# Pro_Trinket_Keyboard_V3_4_a.net
KiCad netlist of a schematic drawn in EAGLE
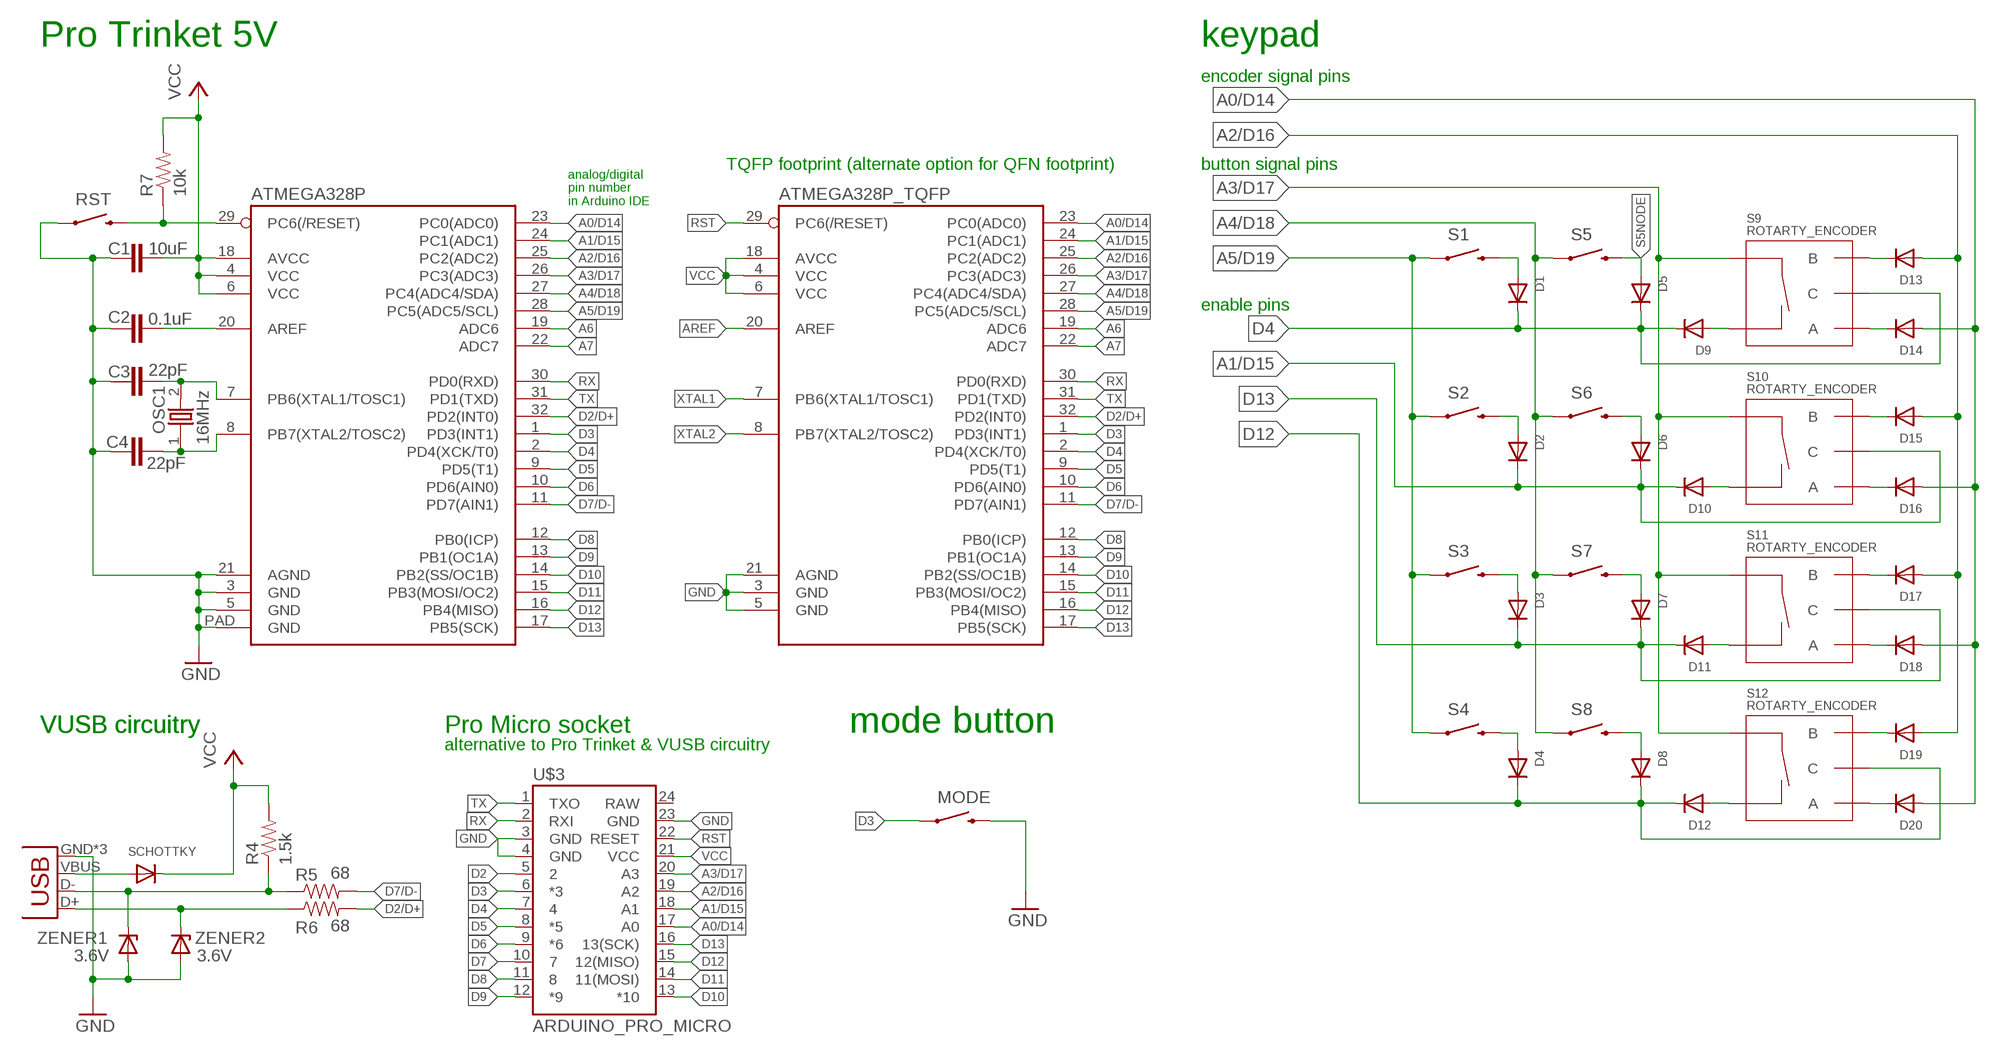
[diagram p0: schematic, sheet 1, part 1 of 2]
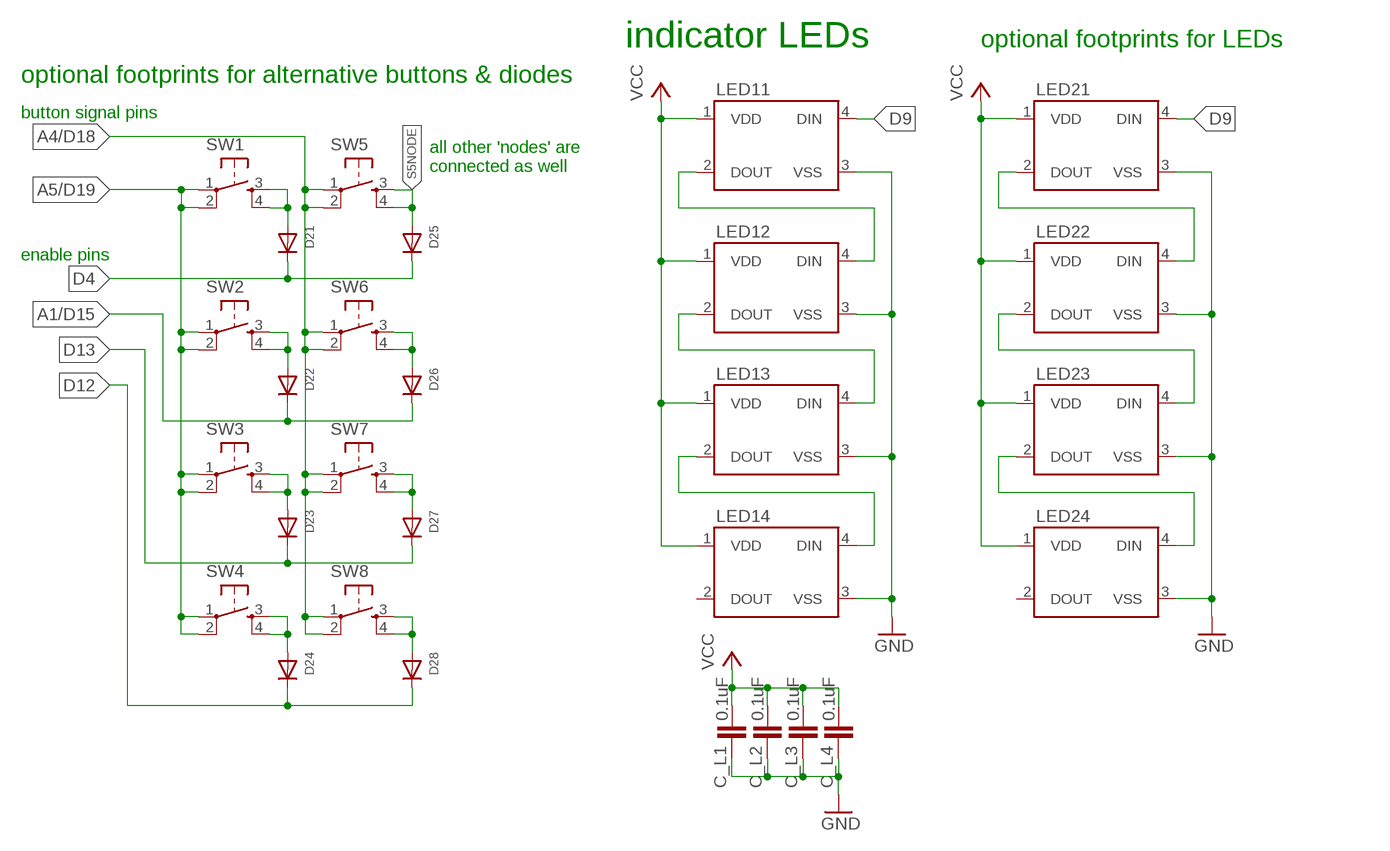
[diagram p1: schematic, sheet 1, part 2 of 2]

(export (version "E")
  (design (tool "Eeschema 10.0.6"))
  (components
    (comp (ref "ATMEGA328P")
      (value "ATMEGA328P_MLFMLF32")
      (footprint "eagle-import:MLF32-PAD")
      (libsource (lib "eagle-import") (part "ATMEGA328P_MLFMLF32"))
    )
    (comp (ref "ATMEGA328P_TQFP")
      (value "ATMEGA328P_TQFP")
      (footprint "eagle-import:TQFP32-08")
      (libsource (lib "eagle-import") (part "ATMEGA328P_TQFP"))
    )
    (comp (ref "C1")
      (value "10uF")
      (footprint "eagle-import:0603-CAP")
      (libsource (lib "eagle-import") (part "10UF-6.3V-20%(0603)"))
    )
    (comp (ref "C2")
      (value "0.1uF")
      (footprint "eagle-import:0603-CAP")
      (libsource (lib "eagle-import") (part "22PF-50V-5%(0603)"))
    )
    (comp (ref "C3")
      (value "22pF")
      (footprint "eagle-import:0603-CAP")
      (libsource (lib "eagle-import") (part "22PF-50V-5%(0603)"))
    )
    (comp (ref "C4")
      (value "22pF")
      (footprint "eagle-import:0603-CAP")
      (libsource (lib "eagle-import") (part "22PF-50V-5%(0603)"))
    )
    (comp (ref "C_L1")
      (value "0.1uF")
      (footprint "eagle-import:0603-CAP")
      (libsource (lib "eagle-import") (part "22PF-50V-5%(0603)"))
    )
    (comp (ref "C_L2")
      (value "0.1uF")
      (footprint "eagle-import:0603-CAP")
      (libsource (lib "eagle-import") (part "22PF-50V-5%(0603)"))
    )
    (comp (ref "C_L3")
      (value "0.1uF")
      (footprint "eagle-import:0603-CAP")
      (libsource (lib "eagle-import") (part "22PF-50V-5%(0603)"))
    )
    (comp (ref "C_L4")
      (value "0.1uF")
      (footprint "eagle-import:0603-CAP")
      (libsource (lib "eagle-import") (part "22PF-50V-5%(0603)"))
    )
    (comp (ref "D1")
      (value "DIODESOD-123")
      (footprint "eagle-import:SOD-123")
      (libsource (lib "eagle-import") (part "DIODESOD-123"))
    )
    (comp (ref "D2")
      (value "DIODESOD-123")
      (footprint "eagle-import:SOD-123")
      (libsource (lib "eagle-import") (part "DIODESOD-123"))
    )
    (comp (ref "D3")
      (value "DIODESOD-123")
      (footprint "eagle-import:SOD-123")
      (libsource (lib "eagle-import") (part "DIODESOD-123"))
    )
    (comp (ref "D4")
      (value "DIODESOD-123")
      (footprint "eagle-import:SOD-123")
      (libsource (lib "eagle-import") (part "DIODESOD-123"))
    )
    (comp (ref "D5")
      (value "DIODESOD-123")
      (footprint "eagle-import:SOD-123")
      (libsource (lib "eagle-import") (part "DIODESOD-123"))
    )
    (comp (ref "D6")
      (value "DIODESOD-123")
      (footprint "eagle-import:SOD-123")
      (libsource (lib "eagle-import") (part "DIODESOD-123"))
    )
    (comp (ref "D7")
      (value "DIODESOD-123")
      (footprint "eagle-import:SOD-123")
      (libsource (lib "eagle-import") (part "DIODESOD-123"))
    )
    (comp (ref "D8")
      (value "DIODESOD-123")
      (footprint "eagle-import:SOD-123")
      (libsource (lib "eagle-import") (part "DIODESOD-123"))
    )
    (comp (ref "D9")
      (value "DIODESOD-123")
      (footprint "eagle-import:SOD-123")
      (libsource (lib "eagle-import") (part "DIODESOD-123"))
    )
    (comp (ref "D10")
      (value "DIODESOD-123")
      (footprint "eagle-import:SOD-123")
      (libsource (lib "eagle-import") (part "DIODESOD-123"))
    )
    (comp (ref "D11")
      (value "DIODESOD-123")
      (footprint "eagle-import:SOD-123")
      (libsource (lib "eagle-import") (part "DIODESOD-123"))
    )
    (comp (ref "D12")
      (value "DIODESOD-123")
      (footprint "eagle-import:SOD-123")
      (libsource (lib "eagle-import") (part "DIODESOD-123"))
    )
    (comp (ref "D13")
      (value "DIODESOD-123")
      (footprint "eagle-import:SOD-123")
      (libsource (lib "eagle-import") (part "DIODESOD-123"))
    )
    (comp (ref "D14")
      (value "DIODESOD-123")
      (footprint "eagle-import:SOD-123")
      (libsource (lib "eagle-import") (part "DIODESOD-123"))
    )
    (comp (ref "D15")
      (value "DIODESOD-123")
      (footprint "eagle-import:SOD-123")
      (libsource (lib "eagle-import") (part "DIODESOD-123"))
    )
    (comp (ref "D16")
      (value "DIODESOD-123")
      (footprint "eagle-import:SOD-123")
      (libsource (lib "eagle-import") (part "DIODESOD-123"))
    )
    (comp (ref "D17")
      (value "DIODESOD-123")
      (footprint "eagle-import:SOD-123")
      (libsource (lib "eagle-import") (part "DIODESOD-123"))
    )
    (comp (ref "D18")
      (value "DIODESOD-123")
      (footprint "eagle-import:SOD-123")
      (libsource (lib "eagle-import") (part "DIODESOD-123"))
    )
    (comp (ref "D19")
      (value "DIODESOD-123")
      (footprint "eagle-import:SOD-123")
      (libsource (lib "eagle-import") (part "DIODESOD-123"))
    )
    (comp (ref "D20")
      (value "DIODESOD-123")
      (footprint "eagle-import:SOD-123")
      (libsource (lib "eagle-import") (part "DIODESOD-123"))
    )
    (comp (ref "D21")
      (value "DIODESOD-123")
      (footprint "eagle-import:SOD-123")
      (libsource (lib "eagle-import") (part "DIODESOD-123"))
    )
    (comp (ref "D22")
      (value "DIODESOD-123")
      (footprint "eagle-import:SOD-123")
      (libsource (lib "eagle-import") (part "DIODESOD-123"))
    )
    (comp (ref "D23")
      (value "DIODESOD-123")
      (footprint "eagle-import:SOD-123")
      (libsource (lib "eagle-import") (part "DIODESOD-123"))
    )
    (comp (ref "D24")
      (value "DIODESOD-123")
      (footprint "eagle-import:SOD-123")
      (libsource (lib "eagle-import") (part "DIODESOD-123"))
    )
    (comp (ref "D25")
      (value "DIODESOD-123")
      (footprint "eagle-import:SOD-123")
      (libsource (lib "eagle-import") (part "DIODESOD-123"))
    )
    (comp (ref "D26")
      (value "DIODESOD-123")
      (footprint "eagle-import:SOD-123")
      (libsource (lib "eagle-import") (part "DIODESOD-123"))
    )
    (comp (ref "D27")
      (value "DIODESOD-123")
      (footprint "eagle-import:SOD-123")
      (libsource (lib "eagle-import") (part "DIODESOD-123"))
    )
    (comp (ref "D28")
      (value "DIODESOD-123")
      (footprint "eagle-import:SOD-123")
      (libsource (lib "eagle-import") (part "DIODESOD-123"))
    )
    (comp (ref "LED11")
      (value "WS2812B")
      (footprint "eagle-import:WS2812B")
      (libsource (lib "eagle-import") (part "WS2812B"))
    )
    (comp (ref "LED12")
      (value "WS2812B")
      (footprint "eagle-import:WS2812B")
      (libsource (lib "eagle-import") (part "WS2812B"))
    )
    (comp (ref "LED13")
      (value "WS2812B")
      (footprint "eagle-import:WS2812B")
      (libsource (lib "eagle-import") (part "WS2812B"))
    )
    (comp (ref "LED14")
      (value "WS2812B")
      (footprint "eagle-import:WS2812B")
      (libsource (lib "eagle-import") (part "WS2812B"))
    )
    (comp (ref "LED21")
      (value "WS2812B")
      (footprint "eagle-import:WS2812B")
      (libsource (lib "eagle-import") (part "WS2812B"))
    )
    (comp (ref "LED22")
      (value "WS2812B")
      (footprint "eagle-import:WS2812B")
      (libsource (lib "eagle-import") (part "WS2812B"))
    )
    (comp (ref "LED23")
      (value "WS2812B")
      (footprint "eagle-import:WS2812B")
      (libsource (lib "eagle-import") (part "WS2812B"))
    )
    (comp (ref "LED24")
      (value "WS2812B")
      (footprint "eagle-import:WS2812B")
      (libsource (lib "eagle-import") (part "WS2812B"))
    )
    (comp (ref "MODE")
      (value "SWITCH-MOMENTARY-2SIDE_EZ")
      (footprint "eagle-import:TACTILE-PTH-SIDEEZ")
      (libsource (lib "eagle-import") (part "SWITCH-MOMENTARY-2SIDE_EZ"))
    )
    (comp (ref "OSC1")
      (value "16MHz")
      (footprint "eagle-import:HC-49U")
      (libsource (lib "eagle-import") (part "OSC-XTAL-HC-49U-SMD"))
    )
    (comp (ref "R4")
      (value "1.5k")
      (footprint "eagle-import:0805")
      (libsource (lib "eagle-import") (part "RESISTOR0805-RES"))
    )
    (comp (ref "R5")
      (value "68")
      (footprint "eagle-import:0805")
      (libsource (lib "eagle-import") (part "RESISTOR0805-RES"))
    )
    (comp (ref "R6")
      (value "68")
      (footprint "eagle-import:0805")
      (libsource (lib "eagle-import") (part "RESISTOR0805-RES"))
    )
    (comp (ref "R7")
      (value "10k")
      (footprint "eagle-import:0805")
      (libsource (lib "eagle-import") (part "RESISTOR0805-RES"))
    )
    (comp (ref "RST")
      (value "SWITCH-MOMENTARY-2SIDE_EZ")
      (footprint "eagle-import:TACTILE-PTH-SIDEEZ")
      (libsource (lib "eagle-import") (part "SWITCH-MOMENTARY-2SIDE_EZ"))
    )
    (comp (ref "S1")
      (value "SWITCH-MOMENTARY-212MM")
      (footprint "eagle-import:TACTILE-PTH-12MM")
      (libsource (lib "eagle-import") (part "SWITCH-MOMENTARY-212MM"))
    )
    (comp (ref "S2")
      (value "SWITCH-MOMENTARY-212MM")
      (footprint "eagle-import:TACTILE-PTH-12MM")
      (libsource (lib "eagle-import") (part "SWITCH-MOMENTARY-212MM"))
    )
    (comp (ref "S3")
      (value "SWITCH-MOMENTARY-212MM")
      (footprint "eagle-import:TACTILE-PTH-12MM")
      (libsource (lib "eagle-import") (part "SWITCH-MOMENTARY-212MM"))
    )
    (comp (ref "S4")
      (value "SWITCH-MOMENTARY-212MM")
      (footprint "eagle-import:TACTILE-PTH-12MM")
      (libsource (lib "eagle-import") (part "SWITCH-MOMENTARY-212MM"))
    )
    (comp (ref "S5")
      (value "SWITCH-MOMENTARY-212MM")
      (footprint "eagle-import:TACTILE-PTH-12MM")
      (libsource (lib "eagle-import") (part "SWITCH-MOMENTARY-212MM"))
    )
    (comp (ref "S6")
      (value "SWITCH-MOMENTARY-212MM")
      (footprint "eagle-import:TACTILE-PTH-12MM")
      (libsource (lib "eagle-import") (part "SWITCH-MOMENTARY-212MM"))
    )
    (comp (ref "S7")
      (value "SWITCH-MOMENTARY-212MM")
      (footprint "eagle-import:TACTILE-PTH-12MM")
      (libsource (lib "eagle-import") (part "SWITCH-MOMENTARY-212MM"))
    )
    (comp (ref "S8")
      (value "SWITCH-MOMENTARY-212MM")
      (footprint "eagle-import:TACTILE-PTH-12MM")
      (libsource (lib "eagle-import") (part "SWITCH-MOMENTARY-212MM"))
    )
    (comp (ref "S9")
      (value "ROTARTY_ENCODER")
      (footprint "eagle-import:ROTARY_ENC_PLAIN")
      (libsource (lib "eagle-import") (part "ROTARTY_ENCODER"))
    )
    (comp (ref "S10")
      (value "ROTARTY_ENCODER")
      (footprint "eagle-import:ROTARY_ENC_PLAIN")
      (libsource (lib "eagle-import") (part "ROTARTY_ENCODER"))
    )
    (comp (ref "S11")
      (value "ROTARTY_ENCODER")
      (footprint "eagle-import:ROTARY_ENC_PLAIN")
      (libsource (lib "eagle-import") (part "ROTARTY_ENCODER"))
    )
    (comp (ref "S12")
      (value "ROTARTY_ENCODER")
      (footprint "eagle-import:ROTARY_ENC_PLAIN")
      (libsource (lib "eagle-import") (part "ROTARTY_ENCODER"))
    )
    (comp (ref "SCHOTTKY")
      (value "DIODESMA")
      (footprint "eagle-import:SMADIODE")
      (libsource (lib "eagle-import") (part "DIODESMA"))
    )
    (comp (ref "SW1")
      (value "TACTILE-SWITCH-PTH")
      (footprint "eagle-import:TAC-SWITCH-PTH")
      (libsource (lib "eagle-import") (part "TACTILE-SWITCH-PTH"))
    )
    (comp (ref "SW2")
      (value "TACTILE-SWITCH-PTH")
      (footprint "eagle-import:TAC-SWITCH-PTH")
      (libsource (lib "eagle-import") (part "TACTILE-SWITCH-PTH"))
    )
    (comp (ref "SW3")
      (value "TACTILE-SWITCH-PTH")
      (footprint "eagle-import:TAC-SWITCH-PTH")
      (libsource (lib "eagle-import") (part "TACTILE-SWITCH-PTH"))
    )
    (comp (ref "SW4")
      (value "TACTILE-SWITCH-PTH")
      (footprint "eagle-import:TAC-SWITCH-PTH")
      (libsource (lib "eagle-import") (part "TACTILE-SWITCH-PTH"))
    )
    (comp (ref "SW5")
      (value "TACTILE-SWITCH-PTH")
      (footprint "eagle-import:TAC-SWITCH-PTH")
      (libsource (lib "eagle-import") (part "TACTILE-SWITCH-PTH"))
    )
    (comp (ref "SW6")
      (value "TACTILE-SWITCH-PTH")
      (footprint "eagle-import:TAC-SWITCH-PTH")
      (libsource (lib "eagle-import") (part "TACTILE-SWITCH-PTH"))
    )
    (comp (ref "SW7")
      (value "TACTILE-SWITCH-PTH")
      (footprint "eagle-import:TAC-SWITCH-PTH")
      (libsource (lib "eagle-import") (part "TACTILE-SWITCH-PTH"))
    )
    (comp (ref "SW8")
      (value "TACTILE-SWITCH-PTH")
      (footprint "eagle-import:TAC-SWITCH-PTH")
      (libsource (lib "eagle-import") (part "TACTILE-SWITCH-PTH"))
    )
    (comp (ref "U$3")
      (value "ARDUINO_PRO_MICRO")
      (footprint "eagle-import:ARDUINO_PRO_MICRO")
      (libsource (lib "eagle-import") (part "ARDUINO_PRO_MICRO"))
    )
    (comp (ref "UUSB")
      (value "USB-MICROB")
      (footprint "eagle-import:USB-MICROB")
      (libsource (lib "eagle-import") (part "USB-MICROB"))
    )
    (comp (ref "ZENER1")
      (value "3.6V")
      (footprint "eagle-import:SOD80C")
      (libsource (lib "eagle-import") (part "ZENER-DIODESOD80C"))
    )
    (comp (ref "ZENER2")
      (value "3.6V")
      (footprint "eagle-import:SOD80C")
      (libsource (lib "eagle-import") (part "ZENER-DIODESOD80C"))
    )
  )
  (nets
    (net (code "1") (name "/L1NODE") (class "Default")
      (node (ref "LED11") (pin "2") (pinfunction "DOUT_2") (pintype "output"))
      (node (ref "LED12") (pin "4") (pinfunction "DIN_4") (pintype "input"))
      (node (ref "LED21") (pin "2") (pinfunction "DOUT_2") (pintype "output"))
      (node (ref "LED22") (pin "4") (pinfunction "DIN_4") (pintype "input"))
    )
    (net (code "2") (name "/L2NODE") (class "Default")
      (node (ref "LED12") (pin "2") (pinfunction "DOUT_2") (pintype "output"))
      (node (ref "LED13") (pin "4") (pinfunction "DIN_4") (pintype "input"))
      (node (ref "LED22") (pin "2") (pinfunction "DOUT_2") (pintype "output"))
      (node (ref "LED23") (pin "4") (pinfunction "DIN_4") (pintype "input"))
    )
    (net (code "3") (name "/L3NODE") (class "Default")
      (node (ref "LED13") (pin "2") (pinfunction "DOUT_2") (pintype "output"))
      (node (ref "LED14") (pin "4") (pinfunction "DIN_4") (pintype "input"))
      (node (ref "LED23") (pin "2") (pinfunction "DOUT_2") (pintype "output"))
      (node (ref "LED24") (pin "4") (pinfunction "DIN_4") (pintype "input"))
    )
    (net (code "4") (name "/S1NODE") (class "Default")
      (node (ref "D1") (pin "A") (pinfunction "A_A") (pintype "passive"))
      (node (ref "D21") (pin "A") (pinfunction "A_A") (pintype "passive"))
      (node (ref "S1") (pin "3") (pinfunction "2_3") (pintype "passive"))
      (node (ref "S1") (pin "4") (pinfunction "2_4") (pintype "passive"))
      (node (ref "SW1") (pin "3") (pinfunction "3_3") (pintype "passive"))
      (node (ref "SW1") (pin "4") (pinfunction "4_4") (pintype "passive"))
    )
    (net (code "5") (name "/S2NODE") (class "Default")
      (node (ref "D2") (pin "A") (pinfunction "A_A") (pintype "passive"))
      (node (ref "D22") (pin "A") (pinfunction "A_A") (pintype "passive"))
      (node (ref "S2") (pin "3") (pinfunction "2_3") (pintype "passive"))
      (node (ref "S2") (pin "4") (pinfunction "2_4") (pintype "passive"))
      (node (ref "SW2") (pin "3") (pinfunction "3_3") (pintype "passive"))
      (node (ref "SW2") (pin "4") (pinfunction "4_4") (pintype "passive"))
    )
    (net (code "6") (name "/S3NODE") (class "Default")
      (node (ref "D23") (pin "A") (pinfunction "A_A") (pintype "passive"))
      (node (ref "D3") (pin "A") (pinfunction "A_A") (pintype "passive"))
      (node (ref "S3") (pin "3") (pinfunction "2_3") (pintype "passive"))
      (node (ref "S3") (pin "4") (pinfunction "2_4") (pintype "passive"))
      (node (ref "SW3") (pin "3") (pinfunction "3_3") (pintype "passive"))
      (node (ref "SW3") (pin "4") (pinfunction "4_4") (pintype "passive"))
    )
    (net (code "7") (name "/S4NODE") (class "Default")
      (node (ref "D24") (pin "A") (pinfunction "A_A") (pintype "passive"))
      (node (ref "D4") (pin "A") (pinfunction "A_A") (pintype "passive"))
      (node (ref "S4") (pin "3") (pinfunction "2_3") (pintype "passive"))
      (node (ref "S4") (pin "4") (pinfunction "2_4") (pintype "passive"))
      (node (ref "SW4") (pin "3") (pinfunction "3_3") (pintype "passive"))
      (node (ref "SW4") (pin "4") (pinfunction "4_4") (pintype "passive"))
    )
    (net (code "8") (name "/S6NODE") (class "Default")
      (node (ref "D26") (pin "A") (pinfunction "A_A") (pintype "passive"))
      (node (ref "D6") (pin "A") (pinfunction "A_A") (pintype "passive"))
      (node (ref "S6") (pin "3") (pinfunction "2_3") (pintype "passive"))
      (node (ref "S6") (pin "4") (pinfunction "2_4") (pintype "passive"))
      (node (ref "SW6") (pin "3") (pinfunction "3_3") (pintype "passive"))
      (node (ref "SW6") (pin "4") (pinfunction "4_4") (pintype "passive"))
    )
    (net (code "9") (name "/S7NODE") (class "Default")
      (node (ref "D27") (pin "A") (pinfunction "A_A") (pintype "passive"))
      (node (ref "D7") (pin "A") (pinfunction "A_A") (pintype "passive"))
      (node (ref "S7") (pin "3") (pinfunction "2_3") (pintype "passive"))
      (node (ref "S7") (pin "4") (pinfunction "2_4") (pintype "passive"))
      (node (ref "SW7") (pin "3") (pinfunction "3_3") (pintype "passive"))
      (node (ref "SW7") (pin "4") (pinfunction "4_4") (pintype "passive"))
    )
    (net (code "10") (name "/S8NODE") (class "Default")
      (node (ref "D28") (pin "A") (pinfunction "A_A") (pintype "passive"))
      (node (ref "D8") (pin "A") (pinfunction "A_A") (pintype "passive"))
      (node (ref "S8") (pin "3") (pinfunction "2_3") (pintype "passive"))
      (node (ref "S8") (pin "4") (pinfunction "2_4") (pintype "passive"))
      (node (ref "SW8") (pin "3") (pinfunction "3_3") (pintype "passive"))
      (node (ref "SW8") (pin "4") (pinfunction "4_4") (pintype "passive"))
    )
    (net (code "11") (name "A0{slash}D14") (class "Default")
      (node (ref "ATMEGA328P") (pin "23") (pinfunction "PC0(ADC0)_23") (pintype "bidirectional"))
      (node (ref "ATMEGA328P_TQFP") (pin "23") (pinfunction "PC0(ADC0)_23") (pintype "bidirectional"))
      (node (ref "D14") (pin "A") (pinfunction "A_A") (pintype "passive"))
      (node (ref "D16") (pin "A") (pinfunction "A_A") (pintype "passive"))
      (node (ref "D18") (pin "A") (pinfunction "A_A") (pintype "passive"))
      (node (ref "D20") (pin "A") (pinfunction "A_A") (pintype "passive"))
      (node (ref "U$3") (pin "17") (pinfunction "A0_17") (pintype "bidirectional"))
    )
    (net (code "12") (name "A1{slash}D15") (class "Default")
      (node (ref "ATMEGA328P") (pin "24") (pinfunction "PC1(ADC1)_24") (pintype "bidirectional"))
      (node (ref "ATMEGA328P_TQFP") (pin "24") (pinfunction "PC1(ADC1)_24") (pintype "bidirectional"))
      (node (ref "D10") (pin "C") (pinfunction "C_C") (pintype "passive"))
      (node (ref "D2") (pin "C") (pinfunction "C_C") (pintype "passive"))
      (node (ref "D22") (pin "C") (pinfunction "C_C") (pintype "passive"))
      (node (ref "D26") (pin "C") (pinfunction "C_C") (pintype "passive"))
      (node (ref "D6") (pin "C") (pinfunction "C_C") (pintype "passive"))
      (node (ref "S10") (pin "C") (pinfunction "C_C") (pintype "bidirectional"))
      (node (ref "U$3") (pin "18") (pinfunction "A1_18") (pintype "bidirectional"))
    )
    (net (code "13") (name "A2{slash}D16") (class "Default")
      (node (ref "ATMEGA328P") (pin "25") (pinfunction "PC2(ADC2)_25") (pintype "bidirectional"))
      (node (ref "ATMEGA328P_TQFP") (pin "25") (pinfunction "PC2(ADC2)_25") (pintype "bidirectional"))
      (node (ref "D13") (pin "A") (pinfunction "A_A") (pintype "passive"))
      (node (ref "D15") (pin "A") (pinfunction "A_A") (pintype "passive"))
      (node (ref "D17") (pin "A") (pinfunction "A_A") (pintype "passive"))
      (node (ref "D19") (pin "A") (pinfunction "A_A") (pintype "passive"))
      (node (ref "U$3") (pin "19") (pinfunction "A2_19") (pintype "bidirectional"))
    )
    (net (code "14") (name "A3{slash}D17") (class "Default")
      (node (ref "ATMEGA328P") (pin "26") (pinfunction "PC3(ADC3)_26") (pintype "bidirectional"))
      (node (ref "ATMEGA328P_TQFP") (pin "26") (pinfunction "PC3(ADC3)_26") (pintype "bidirectional"))
      (node (ref "S10") (pin "SW+") (pinfunction "SW+_SW+") (pintype "bidirectional"))
      (node (ref "S11") (pin "SW+") (pinfunction "SW+_SW+") (pintype "bidirectional"))
      (node (ref "S12") (pin "SW+") (pinfunction "SW+_SW+") (pintype "bidirectional"))
      (node (ref "S9") (pin "SW+") (pinfunction "SW+_SW+") (pintype "bidirectional"))
      (node (ref "U$3") (pin "20") (pinfunction "A3_20") (pintype "bidirectional"))
    )
    (net (code "15") (name "A4{slash}D18") (class "Default")
      (node (ref "ATMEGA328P") (pin "27") (pinfunction "PC4(ADC4/SDA)_27") (pintype "bidirectional"))
      (node (ref "ATMEGA328P_TQFP") (pin "27") (pinfunction "PC4(ADC4/SDA)_27") (pintype "bidirectional"))
      (node (ref "S5") (pin "1") (pinfunction "1_1") (pintype "passive"))
      (node (ref "S5") (pin "2") (pinfunction "1_2") (pintype "passive"))
      (node (ref "S6") (pin "1") (pinfunction "1_1") (pintype "passive"))
      (node (ref "S6") (pin "2") (pinfunction "1_2") (pintype "passive"))
      (node (ref "S7") (pin "1") (pinfunction "1_1") (pintype "passive"))
      (node (ref "S7") (pin "2") (pinfunction "1_2") (pintype "passive"))
      (node (ref "S8") (pin "1") (pinfunction "1_1") (pintype "passive"))
      (node (ref "S8") (pin "2") (pinfunction "1_2") (pintype "passive"))
      (node (ref "SW5") (pin "1") (pinfunction "1_1") (pintype "passive"))
      (node (ref "SW5") (pin "2") (pinfunction "2_2") (pintype "passive"))
      (node (ref "SW6") (pin "1") (pinfunction "1_1") (pintype "passive"))
      (node (ref "SW6") (pin "2") (pinfunction "2_2") (pintype "passive"))
      (node (ref "SW7") (pin "1") (pinfunction "1_1") (pintype "passive"))
      (node (ref "SW7") (pin "2") (pinfunction "2_2") (pintype "passive"))
      (node (ref "SW8") (pin "1") (pinfunction "1_1") (pintype "passive"))
      (node (ref "SW8") (pin "2") (pinfunction "2_2") (pintype "passive"))
    )
    (net (code "16") (name "A5{slash}D19") (class "Default")
      (node (ref "ATMEGA328P") (pin "28") (pinfunction "PC5(ADC5/SCL)_28") (pintype "bidirectional"))
      (node (ref "ATMEGA328P_TQFP") (pin "28") (pinfunction "PC5(ADC5/SCL)_28") (pintype "bidirectional"))
      (node (ref "S1") (pin "1") (pinfunction "1_1") (pintype "passive"))
      (node (ref "S1") (pin "2") (pinfunction "1_2") (pintype "passive"))
      (node (ref "S2") (pin "1") (pinfunction "1_1") (pintype "passive"))
      (node (ref "S2") (pin "2") (pinfunction "1_2") (pintype "passive"))
      (node (ref "S3") (pin "1") (pinfunction "1_1") (pintype "passive"))
      (node (ref "S3") (pin "2") (pinfunction "1_2") (pintype "passive"))
      (node (ref "S4") (pin "1") (pinfunction "1_1") (pintype "passive"))
      (node (ref "S4") (pin "2") (pinfunction "1_2") (pintype "passive"))
      (node (ref "SW1") (pin "1") (pinfunction "1_1") (pintype "passive"))
      (node (ref "SW1") (pin "2") (pinfunction "2_2") (pintype "passive"))
      (node (ref "SW2") (pin "1") (pinfunction "1_1") (pintype "passive"))
      (node (ref "SW2") (pin "2") (pinfunction "2_2") (pintype "passive"))
      (node (ref "SW3") (pin "1") (pinfunction "1_1") (pintype "passive"))
      (node (ref "SW3") (pin "2") (pinfunction "2_2") (pintype "passive"))
      (node (ref "SW4") (pin "1") (pinfunction "1_1") (pintype "passive"))
      (node (ref "SW4") (pin "2") (pinfunction "2_2") (pintype "passive"))
    )
    (net (code "17") (name "A6") (class "Default")
      (node (ref "ATMEGA328P") (pin "19") (pinfunction "ADC6_19") (pintype "bidirectional"))
      (node (ref "ATMEGA328P_TQFP") (pin "19") (pinfunction "ADC6_19") (pintype "bidirectional"))
    )
    (net (code "18") (name "A7") (class "Default")
      (node (ref "ATMEGA328P") (pin "22") (pinfunction "ADC7_22") (pintype "bidirectional"))
      (node (ref "ATMEGA328P_TQFP") (pin "22") (pinfunction "ADC7_22") (pintype "bidirectional"))
    )
    (net (code "19") (name "AREF") (class "Default")
      (node (ref "ATMEGA328P") (pin "20") (pinfunction "AREF_20") (pintype "bidirectional"))
      (node (ref "ATMEGA328P_TQFP") (pin "20") (pinfunction "AREF_20") (pintype "bidirectional"))
      (node (ref "C2") (pin "2") (pinfunction "2_2") (pintype "passive"))
    )
    (net (code "20") (name "D2") (class "Default")
      (node (ref "U$3") (pin "5") (pinfunction "2_5") (pintype "bidirectional"))
    )
    (net (code "21") (name "D2{slash}D+") (class "Default")
      (node (ref "ATMEGA328P") (pin "32") (pinfunction "PD2(INT0)_32") (pintype "bidirectional"))
      (node (ref "ATMEGA328P_TQFP") (pin "32") (pinfunction "PD2(INT0)_32") (pintype "bidirectional"))
      (node (ref "R6") (pin "2") (pinfunction "2_2") (pintype "passive"))
    )
    (net (code "22") (name "D3") (class "Default")
      (node (ref "ATMEGA328P") (pin "1") (pinfunction "PD3(INT1)_1") (pintype "bidirectional"))
      (node (ref "ATMEGA328P_TQFP") (pin "1") (pinfunction "PD3(INT1)_1") (pintype "bidirectional"))
      (node (ref "MODE") (pin "1") (pinfunction "1_1") (pintype "passive"))
      (node (ref "U$3") (pin "6") (pinfunction "*3_6") (pintype "bidirectional"))
    )
    (net (code "23") (name "D4") (class "Default")
      (node (ref "ATMEGA328P") (pin "2") (pinfunction "PD4(XCK/T0)_2") (pintype "bidirectional"))
      (node (ref "ATMEGA328P_TQFP") (pin "2") (pinfunction "PD4(XCK/T0)_2") (pintype "bidirectional"))
      (node (ref "D1") (pin "C") (pinfunction "C_C") (pintype "passive"))
      (node (ref "D21") (pin "C") (pinfunction "C_C") (pintype "passive"))
      (node (ref "D25") (pin "C") (pinfunction "C_C") (pintype "passive"))
      (node (ref "D5") (pin "C") (pinfunction "C_C") (pintype "passive"))
      (node (ref "D9") (pin "C") (pinfunction "C_C") (pintype "passive"))
      (node (ref "S9") (pin "C") (pinfunction "C_C") (pintype "bidirectional"))
      (node (ref "U$3") (pin "7") (pinfunction "4_7") (pintype "bidirectional"))
    )
    (net (code "24") (name "D5") (class "Default")
      (node (ref "ATMEGA328P") (pin "9") (pinfunction "PD5(T1)_9") (pintype "bidirectional"))
      (node (ref "ATMEGA328P_TQFP") (pin "9") (pinfunction "PD5(T1)_9") (pintype "bidirectional"))
      (node (ref "U$3") (pin "8") (pinfunction "*5_8") (pintype "bidirectional"))
    )
    (net (code "25") (name "D6") (class "Default")
      (node (ref "ATMEGA328P") (pin "10") (pinfunction "PD6(AIN0)_10") (pintype "bidirectional"))
      (node (ref "ATMEGA328P_TQFP") (pin "10") (pinfunction "PD6(AIN0)_10") (pintype "bidirectional"))
      (node (ref "U$3") (pin "9") (pinfunction "*6_9") (pintype "bidirectional"))
    )
    (net (code "26") (name "D7") (class "Default")
      (node (ref "U$3") (pin "10") (pinfunction "7_10") (pintype "bidirectional"))
    )
    (net (code "27") (name "D7{slash}D-") (class "Default")
      (node (ref "ATMEGA328P") (pin "11") (pinfunction "PD7(AIN1)_11") (pintype "bidirectional"))
      (node (ref "ATMEGA328P_TQFP") (pin "11") (pinfunction "PD7(AIN1)_11") (pintype "bidirectional"))
      (node (ref "R5") (pin "2") (pinfunction "2_2") (pintype "passive"))
    )
    (net (code "28") (name "D8") (class "Default")
      (node (ref "ATMEGA328P") (pin "12") (pinfunction "PB0(ICP)_12") (pintype "bidirectional"))
      (node (ref "ATMEGA328P_TQFP") (pin "12") (pinfunction "PB0(ICP)_12") (pintype "bidirectional"))
      (node (ref "U$3") (pin "11") (pinfunction "8_11") (pintype "bidirectional"))
    )
    (net (code "29") (name "D9") (class "Default")
      (node (ref "ATMEGA328P") (pin "13") (pinfunction "PB1(OC1A)_13") (pintype "bidirectional"))
      (node (ref "ATMEGA328P_TQFP") (pin "13") (pinfunction "PB1(OC1A)_13") (pintype "bidirectional"))
      (node (ref "LED11") (pin "4") (pinfunction "DIN_4") (pintype "input"))
      (node (ref "LED21") (pin "4") (pinfunction "DIN_4") (pintype "input"))
      (node (ref "U$3") (pin "12") (pinfunction "*9_12") (pintype "bidirectional"))
    )
    (net (code "30") (name "D10") (class "Default")
      (node (ref "ATMEGA328P") (pin "14") (pinfunction "PB2(SS/OC1B)_14") (pintype "bidirectional"))
      (node (ref "ATMEGA328P_TQFP") (pin "14") (pinfunction "PB2(SS/OC1B)_14") (pintype "bidirectional"))
      (node (ref "U$3") (pin "13") (pinfunction "*10_13") (pintype "bidirectional"))
    )
    (net (code "31") (name "D11") (class "Default")
      (node (ref "ATMEGA328P") (pin "15") (pinfunction "PB3(MOSI/OC2)_15") (pintype "bidirectional"))
      (node (ref "ATMEGA328P_TQFP") (pin "15") (pinfunction "PB3(MOSI/OC2)_15") (pintype "bidirectional"))
      (node (ref "U$3") (pin "14") (pinfunction "11(MOSI)_14") (pintype "bidirectional"))
    )
    (net (code "32") (name "D12") (class "Default")
      (node (ref "ATMEGA328P") (pin "16") (pinfunction "PB4(MISO)_16") (pintype "bidirectional"))
      (node (ref "ATMEGA328P_TQFP") (pin "16") (pinfunction "PB4(MISO)_16") (pintype "bidirectional"))
      (node (ref "D12") (pin "C") (pinfunction "C_C") (pintype "passive"))
      (node (ref "D24") (pin "C") (pinfunction "C_C") (pintype "passive"))
      (node (ref "D28") (pin "C") (pinfunction "C_C") (pintype "passive"))
      (node (ref "D4") (pin "C") (pinfunction "C_C") (pintype "passive"))
      (node (ref "D8") (pin "C") (pinfunction "C_C") (pintype "passive"))
      (node (ref "S12") (pin "C") (pinfunction "C_C") (pintype "bidirectional"))
      (node (ref "U$3") (pin "15") (pinfunction "12(MISO)_15") (pintype "bidirectional"))
    )
    (net (code "33") (name "D13") (class "Default")
      (node (ref "ATMEGA328P") (pin "17") (pinfunction "PB5(SCK)_17") (pintype "bidirectional"))
      (node (ref "ATMEGA328P_TQFP") (pin "17") (pinfunction "PB5(SCK)_17") (pintype "bidirectional"))
      (node (ref "D11") (pin "C") (pinfunction "C_C") (pintype "passive"))
      (node (ref "D23") (pin "C") (pinfunction "C_C") (pintype "passive"))
      (node (ref "D27") (pin "C") (pinfunction "C_C") (pintype "passive"))
      (node (ref "D3") (pin "C") (pinfunction "C_C") (pintype "passive"))
      (node (ref "D7") (pin "C") (pinfunction "C_C") (pintype "passive"))
      (node (ref "S11") (pin "C") (pinfunction "C_C") (pintype "bidirectional"))
      (node (ref "U$3") (pin "16") (pinfunction "13(SCK)_16") (pintype "bidirectional"))
    )
    (net (code "34") (name "GND") (class "Default")
      (node (ref "ATMEGA328P") (pin "21") (pinfunction "AGND_21") (pintype "bidirectional"))
      (node (ref "ATMEGA328P") (pin "3") (pinfunction "GND_3") (pintype "bidirectional"))
      (node (ref "ATMEGA328P") (pin "5") (pinfunction "GND_5") (pintype "bidirectional"))
      (node (ref "ATMEGA328P") (pin "PAD") (pinfunction "GND_PAD") (pintype "bidirectional"))
      (node (ref "ATMEGA328P_TQFP") (pin "21") (pinfunction "AGND_21") (pintype "bidirectional"))
      (node (ref "ATMEGA328P_TQFP") (pin "3") (pinfunction "GND_3") (pintype "bidirectional"))
      (node (ref "ATMEGA328P_TQFP") (pin "5") (pinfunction "GND_5") (pintype "bidirectional"))
      (node (ref "C1") (pin "1") (pinfunction "1_1") (pintype "passive"))
      (node (ref "C2") (pin "1") (pinfunction "1_1") (pintype "passive"))
      (node (ref "C3") (pin "1") (pinfunction "1_1") (pintype "passive"))
      (node (ref "C4") (pin "2") (pinfunction "2_2") (pintype "passive"))
      (node (ref "C_L1") (pin "1") (pinfunction "1_1") (pintype "passive"))
      (node (ref "C_L2") (pin "1") (pinfunction "1_1") (pintype "passive"))
      (node (ref "C_L3") (pin "1") (pinfunction "1_1") (pintype "passive"))
      (node (ref "C_L4") (pin "1") (pinfunction "1_1") (pintype "passive"))
      (node (ref "LED11") (pin "3") (pinfunction "VSS_3") (pintype "power_in"))
      (node (ref "LED12") (pin "3") (pinfunction "VSS_3") (pintype "power_in"))
      (node (ref "LED13") (pin "3") (pinfunction "VSS_3") (pintype "power_in"))
      (node (ref "LED14") (pin "3") (pinfunction "VSS_3") (pintype "power_in"))
      (node (ref "LED21") (pin "3") (pinfunction "VSS_3") (pintype "power_in"))
      (node (ref "LED22") (pin "3") (pinfunction "VSS_3") (pintype "power_in"))
      (node (ref "LED23") (pin "3") (pinfunction "VSS_3") (pintype "power_in"))
      (node (ref "LED24") (pin "3") (pinfunction "VSS_3") (pintype "power_in"))
      (node (ref "MODE") (pin "2") (pinfunction "2_2") (pintype "passive"))
      (node (ref "RST") (pin "1") (pinfunction "1_1") (pintype "passive"))
      (node (ref "U$3") (pin "23") (pinfunction "GND_23") (pintype "bidirectional"))
      (node (ref "U$3") (pin "3") (pinfunction "GND_3") (pintype "bidirectional"))
      (node (ref "U$3") (pin "4") (pinfunction "GND_4") (pintype "bidirectional"))
      (node (ref "UUSB") (pin "GND") (pinfunction "GND_GND") (pintype "bidirectional"))
      (node (ref "UUSB") (pin "MT1") (pinfunction "GND_MT1") (pintype "bidirectional"))
      (node (ref "UUSB") (pin "MT2") (pinfunction "GND_MT2") (pintype "bidirectional"))
      (node (ref "ZENER1") (pin "A") (pinfunction "A_A") (pintype "passive"))
      (node (ref "ZENER2") (pin "A") (pinfunction "A_A") (pintype "passive"))
    )
    (net (code "35") (name "Net-(D9-PadA)") (class "Default")
      (node (ref "D9") (pin "A") (pinfunction "A_A") (pintype "passive"))
      (node (ref "S9") (pin "SW-") (pinfunction "SW-_SW-") (pintype "bidirectional"))
    )
    (net (code "36") (name "Net-(D10-PadA)") (class "Default")
      (node (ref "D10") (pin "A") (pinfunction "A_A") (pintype "passive"))
      (node (ref "S10") (pin "SW-") (pinfunction "SW-_SW-") (pintype "bidirectional"))
    )
    (net (code "37") (name "Net-(D11-PadA)") (class "Default")
      (node (ref "D11") (pin "A") (pinfunction "A_A") (pintype "passive"))
      (node (ref "S11") (pin "SW-") (pinfunction "SW-_SW-") (pintype "bidirectional"))
    )
    (net (code "38") (name "Net-(D12-PadA)") (class "Default")
      (node (ref "D12") (pin "A") (pinfunction "A_A") (pintype "passive"))
      (node (ref "S12") (pin "SW-") (pinfunction "SW-_SW-") (pintype "bidirectional"))
    )
    (net (code "39") (name "Net-(D13-PadC)") (class "Default")
      (node (ref "D13") (pin "C") (pinfunction "C_C") (pintype "passive"))
      (node (ref "S9") (pin "B") (pinfunction "B_B") (pintype "bidirectional"))
    )
    (net (code "40") (name "Net-(D14-PadC)") (class "Default")
      (node (ref "D14") (pin "C") (pinfunction "C_C") (pintype "passive"))
      (node (ref "S9") (pin "A") (pinfunction "A_A") (pintype "bidirectional"))
    )
    (net (code "41") (name "Net-(D15-PadC)") (class "Default")
      (node (ref "D15") (pin "C") (pinfunction "C_C") (pintype "passive"))
      (node (ref "S10") (pin "B") (pinfunction "B_B") (pintype "bidirectional"))
    )
    (net (code "42") (name "Net-(D16-PadC)") (class "Default")
      (node (ref "D16") (pin "C") (pinfunction "C_C") (pintype "passive"))
      (node (ref "S10") (pin "A") (pinfunction "A_A") (pintype "bidirectional"))
    )
    (net (code "43") (name "Net-(D17-PadC)") (class "Default")
      (node (ref "D17") (pin "C") (pinfunction "C_C") (pintype "passive"))
      (node (ref "S11") (pin "B") (pinfunction "B_B") (pintype "bidirectional"))
    )
    (net (code "44") (name "Net-(D18-PadC)") (class "Default")
      (node (ref "D18") (pin "C") (pinfunction "C_C") (pintype "passive"))
      (node (ref "S11") (pin "A") (pinfunction "A_A") (pintype "bidirectional"))
    )
    (net (code "45") (name "Net-(D19-PadC)") (class "Default")
      (node (ref "D19") (pin "C") (pinfunction "C_C") (pintype "passive"))
      (node (ref "S12") (pin "B") (pinfunction "B_B") (pintype "bidirectional"))
    )
    (net (code "46") (name "Net-(D20-PadC)") (class "Default")
      (node (ref "D20") (pin "C") (pinfunction "C_C") (pintype "passive"))
      (node (ref "S12") (pin "A") (pinfunction "A_A") (pintype "bidirectional"))
    )
    (net (code "47") (name "Net-(R4-Pad1)") (class "Default")
      (node (ref "R4") (pin "1") (pinfunction "1_1") (pintype "passive"))
      (node (ref "R5") (pin "1") (pinfunction "1_1") (pintype "passive"))
      (node (ref "UUSB") (pin "D-") (pinfunction "D-_D-") (pintype "bidirectional"))
      (node (ref "ZENER1") (pin "C") (pinfunction "C_C") (pintype "passive"))
    )
    (net (code "48") (name "Net-(R6-Pad1)") (class "Default")
      (node (ref "R6") (pin "1") (pinfunction "1_1") (pintype "passive"))
      (node (ref "UUSB") (pin "D+") (pinfunction "D+_D+") (pintype "bidirectional"))
      (node (ref "ZENER2") (pin "C") (pinfunction "C_C") (pintype "passive"))
    )
    (net (code "49") (name "Net-(SCHOTTKY-PadA)") (class "Default")
      (node (ref "SCHOTTKY") (pin "A") (pinfunction "A_A") (pintype "passive"))
      (node (ref "UUSB") (pin "VBUS") (pinfunction "VBUS_VBUS") (pintype "bidirectional"))
    )
    (net (code "50") (name "RST") (class "Default")
      (node (ref "ATMEGA328P") (pin "29") (pinfunction "PC6(/RESET)_29") (pintype "bidirectional"))
      (node (ref "ATMEGA328P_TQFP") (pin "29") (pinfunction "PC6(/RESET)_29") (pintype "bidirectional"))
      (node (ref "R7") (pin "1") (pinfunction "1_1") (pintype "passive"))
      (node (ref "RST") (pin "2") (pinfunction "2_2") (pintype "passive"))
      (node (ref "U$3") (pin "22") (pinfunction "RESET_22") (pintype "bidirectional"))
    )
    (net (code "51") (name "RX") (class "Default")
      (node (ref "ATMEGA328P") (pin "30") (pinfunction "PD0(RXD)_30") (pintype "bidirectional"))
      (node (ref "ATMEGA328P_TQFP") (pin "30") (pinfunction "PD0(RXD)_30") (pintype "bidirectional"))
      (node (ref "U$3") (pin "2") (pinfunction "RXI_2") (pintype "bidirectional"))
    )
    (net (code "52") (name "S5NODE") (class "Default")
      (node (ref "D25") (pin "A") (pinfunction "A_A") (pintype "passive"))
      (node (ref "D5") (pin "A") (pinfunction "A_A") (pintype "passive"))
      (node (ref "S5") (pin "3") (pinfunction "2_3") (pintype "passive"))
      (node (ref "S5") (pin "4") (pinfunction "2_4") (pintype "passive"))
      (node (ref "SW5") (pin "3") (pinfunction "3_3") (pintype "passive"))
      (node (ref "SW5") (pin "4") (pinfunction "4_4") (pintype "passive"))
    )
    (net (code "53") (name "TX") (class "Default")
      (node (ref "ATMEGA328P") (pin "31") (pinfunction "PD1(TXD)_31") (pintype "bidirectional"))
      (node (ref "ATMEGA328P_TQFP") (pin "31") (pinfunction "PD1(TXD)_31") (pintype "bidirectional"))
      (node (ref "U$3") (pin "1") (pinfunction "TXO_1") (pintype "bidirectional"))
    )
    (net (code "54") (name "VCC") (class "Default")
      (node (ref "ATMEGA328P") (pin "18") (pinfunction "AVCC_18") (pintype "bidirectional"))
      (node (ref "ATMEGA328P") (pin "4") (pinfunction "VCC_4") (pintype "bidirectional"))
      (node (ref "ATMEGA328P") (pin "6") (pinfunction "VCC_6") (pintype "bidirectional"))
      (node (ref "ATMEGA328P_TQFP") (pin "18") (pinfunction "AVCC_18") (pintype "bidirectional"))
      (node (ref "ATMEGA328P_TQFP") (pin "4") (pinfunction "VCC_4") (pintype "bidirectional"))
      (node (ref "ATMEGA328P_TQFP") (pin "6") (pinfunction "VCC_6") (pintype "bidirectional"))
      (node (ref "C1") (pin "2") (pinfunction "2_2") (pintype "passive"))
      (node (ref "C_L1") (pin "2") (pinfunction "2_2") (pintype "passive"))
      (node (ref "C_L2") (pin "2") (pinfunction "2_2") (pintype "passive"))
      (node (ref "C_L3") (pin "2") (pinfunction "2_2") (pintype "passive"))
      (node (ref "C_L4") (pin "2") (pinfunction "2_2") (pintype "passive"))
      (node (ref "LED11") (pin "1") (pinfunction "VDD_1") (pintype "power_in"))
      (node (ref "LED12") (pin "1") (pinfunction "VDD_1") (pintype "power_in"))
      (node (ref "LED13") (pin "1") (pinfunction "VDD_1") (pintype "power_in"))
      (node (ref "LED14") (pin "1") (pinfunction "VDD_1") (pintype "power_in"))
      (node (ref "LED21") (pin "1") (pinfunction "VDD_1") (pintype "power_in"))
      (node (ref "LED22") (pin "1") (pinfunction "VDD_1") (pintype "power_in"))
      (node (ref "LED23") (pin "1") (pinfunction "VDD_1") (pintype "power_in"))
      (node (ref "LED24") (pin "1") (pinfunction "VDD_1") (pintype "power_in"))
      (node (ref "R4") (pin "2") (pinfunction "2_2") (pintype "passive"))
      (node (ref "R7") (pin "2") (pinfunction "2_2") (pintype "passive"))
      (node (ref "SCHOTTKY") (pin "C") (pinfunction "C_C") (pintype "passive"))
      (node (ref "U$3") (pin "21") (pinfunction "VCC_21") (pintype "bidirectional"))
    )
    (net (code "55") (name "XTAL1") (class "Default")
      (node (ref "ATMEGA328P") (pin "7") (pinfunction "PB6(XTAL1/TOSC1)_7") (pintype "bidirectional"))
      (node (ref "ATMEGA328P_TQFP") (pin "7") (pinfunction "PB6(XTAL1/TOSC1)_7") (pintype "bidirectional"))
      (node (ref "C3") (pin "2") (pinfunction "2_2") (pintype "passive"))
      (node (ref "OSC1") (pin "2") (pinfunction "2_2") (pintype "passive"))
    )
    (net (code "56") (name "XTAL2") (class "Default")
      (node (ref "ATMEGA328P") (pin "8") (pinfunction "PB7(XTAL2/TOSC2)_8") (pintype "bidirectional"))
      (node (ref "ATMEGA328P_TQFP") (pin "8") (pinfunction "PB7(XTAL2/TOSC2)_8") (pintype "bidirectional"))
      (node (ref "C4") (pin "1") (pinfunction "1_1") (pintype "passive"))
      (node (ref "OSC1") (pin "1") (pinfunction "1_1") (pintype "passive"))
    )
    (net (code "57") (name "unconnected-(LED14-DOUT-Pad2)") (class "Default")
      (node (ref "LED14") (pin "2") (pinfunction "DOUT_2") (pintype "output"))
    )
    (net (code "58") (name "unconnected-(LED24-DOUT-Pad2)") (class "Default")
      (node (ref "LED24") (pin "2") (pinfunction "DOUT_2") (pintype "output"))
    )
    (net (code "59") (name "unconnected-(U$3-RAW-Pad24)") (class "Default")
      (node (ref "U$3") (pin "24") (pinfunction "RAW_24") (pintype "bidirectional"))
    )
  )
)
